# heatbed.net
KiCad netlist of a schematic drawn in Altium Designer
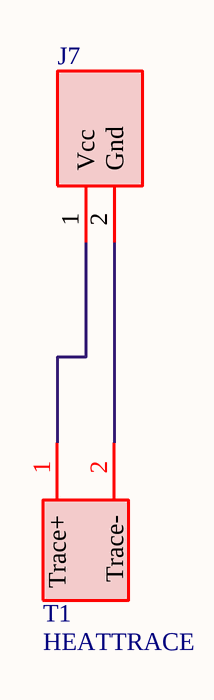
[diagram p0: heatbed.SchDoc]

(export (version "E")
  (design (tool "Eeschema 10.0.6"))
  (components
    (comp (ref "J7")
      (value "CON_F1x2Pin")
      (footprint "CON_F1x2Pin")
      (description "Connector")
      (fields (field (name "MANUFACTURER_PART_NUMBER") "SMC-1-02-1-GT"))
      (libsource (lib "SolderIron") (part "CON_F1x2Pin"))
    )
    (comp (ref "T1") (value "HEATTRACE") (libsource (lib "SolderIron") (part "HEATTRACE")))
  )
  (nets
    (net (code "1") (name "Net-(J7-Gnd)") (class "Default")
      (node (ref "J7") (pin "2") (pinfunction "Gnd_2") (pintype "passive"))
      (node (ref "T1") (pin "2") (pinfunction "Trace-_2") (pintype "passive"))
    )
    (net (code "2") (name "Net-(J7-Vcc)") (class "Default")
      (node (ref "J7") (pin "1") (pinfunction "Vcc_1") (pintype "passive"))
      (node (ref "T1") (pin "1") (pinfunction "Trace+_1") (pintype "passive"))
    )
  )
)
